# Venus638FLPX-L.net
KiCad netlist of a schematic drawn in EAGLE
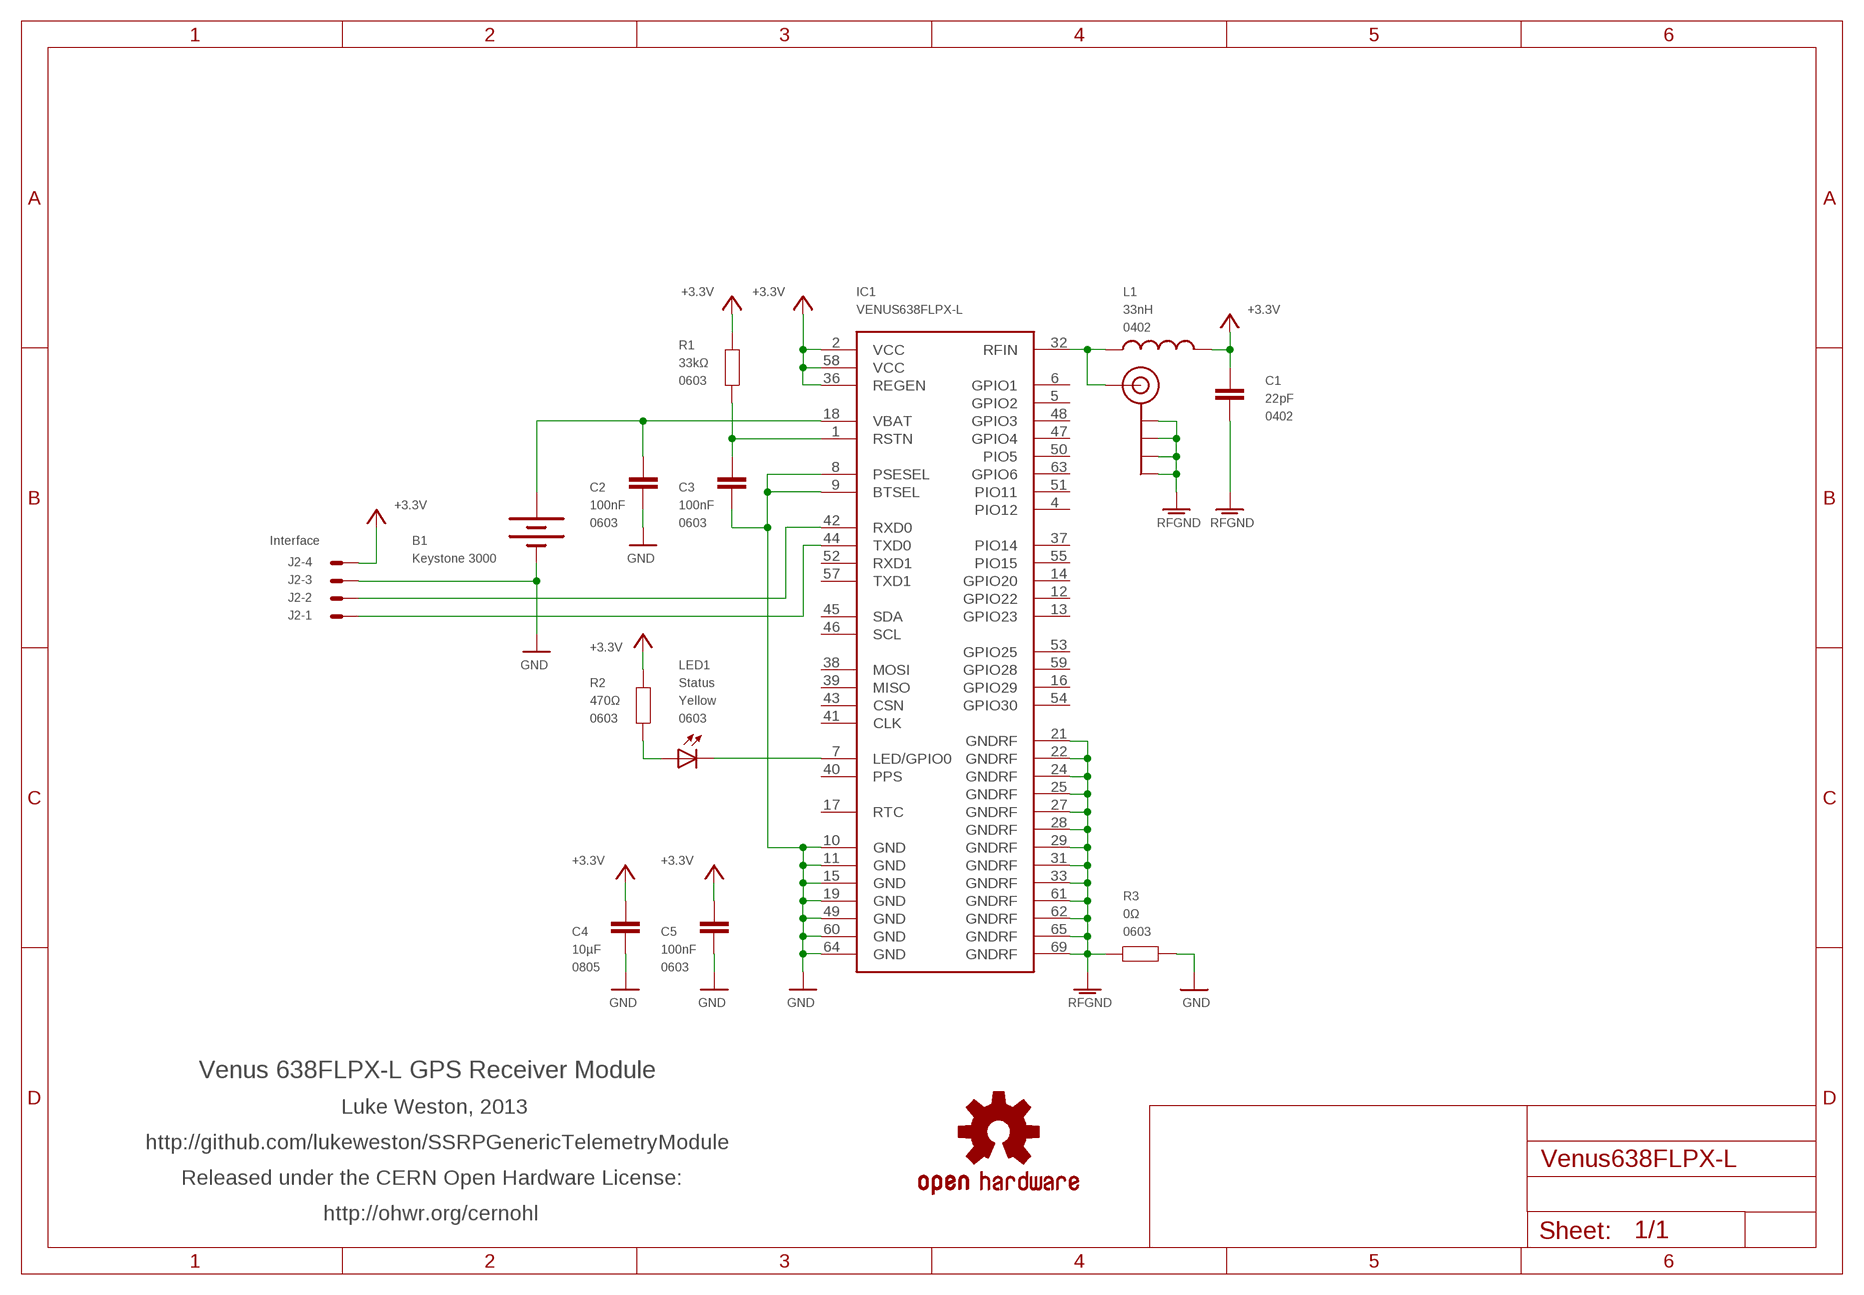
[diagram p0: schematic, sheet 1]

(export (version "E")
  (design (tool "Eeschema 10.0.6"))
  (components
    (comp (ref "B1")
      (value "Keystone 3000")
      (footprint "eagle-import:BATTCON_12MM")
      (libsource (lib "eagle-import") (part "BATTERY12MM"))
    )
    (comp (ref "C1")
      (value "22pF")
      (footprint "eagle-import:C0402")
      (fields (field (name "PACKAGE") "0402"))
      (libsource (lib "eagle-import") (part "CAP0402"))
    )
    (comp (ref "C2")
      (value "100nF")
      (footprint "eagle-import:0603")
      (fields (field (name "PACKAGE") "0603"))
      (libsource (lib "eagle-import") (part "CAP0603"))
    )
    (comp (ref "C3")
      (value "100nF")
      (footprint "eagle-import:0603")
      (fields (field (name "PACKAGE") "0603"))
      (libsource (lib "eagle-import") (part "CAP0603"))
    )
    (comp (ref "C4")
      (value "10µF")
      (footprint "eagle-import:0805")
      (fields (field (name "PACKAGE") "0805"))
      (libsource (lib "eagle-import") (part "CAP0805"))
    )
    (comp (ref "C5")
      (value "100nF")
      (footprint "eagle-import:0603")
      (fields (field (name "PACKAGE") "0603"))
      (libsource (lib "eagle-import") (part "CAP0603"))
    )
    (comp (ref "IC1")
      (value "VENUS638FLPX-L")
      (footprint "eagle-import:VENUS638FLPX")
      (libsource (lib "eagle-import") (part "VENUS638FLPX-L"))
    )
    (comp (ref "J1")
      (value "Antenna")
      (footprint "eagle-import:SMA-EDGE")
      (libsource (lib "eagle-import") (part "SMA_EDGE"))
    )
    (comp (ref "J2")
      (value "Interface")
      (footprint "eagle-import:22-23-2041")
      (fields (field (name "MF") "MOLEX") (field (name "MPN") "22-23-2041"))
      (libsource (lib "eagle-import") (part "22-23-2041"))
    )
    (comp (ref "L1")
      (value "33nH")
      (footprint "eagle-import:C0402")
      (fields (field (name "PACKAGE") "0402"))
      (libsource (lib "eagle-import") (part "INDUCTOR0402"))
    )
    (comp (ref "LED1")
      (value "Status")
      (footprint "eagle-import:LED-0603")
      (fields (field (name "COLOUR") "Yellow") (field (name "PACKAGE") "0603"))
      (libsource (lib "eagle-import") (part "LED0603"))
    )
    (comp (ref "R1")
      (value "33kΩ")
      (footprint "eagle-import:0603")
      (fields (field (name "PACKAGE") "0603"))
      (libsource (lib "eagle-import") (part "RESISTOR0603"))
    )
    (comp (ref "R2")
      (value "470Ω")
      (footprint "eagle-import:0603")
      (fields (field (name "PACKAGE") "0603"))
      (libsource (lib "eagle-import") (part "RESISTOR0603"))
    )
    (comp (ref "R3")
      (value "0Ω")
      (footprint "eagle-import:0603")
      (fields (field (name "PACKAGE") "0603"))
      (libsource (lib "eagle-import") (part "RESISTOR0603"))
    )
    (comp (ref "SY")
      (value "OSHW-LOGOS")
      (footprint "eagle-import:OSHW-LOGO-S")
      (libsource (lib "eagle-import") (part "OSHW-LOGOS"))
    )
  )
  (nets
    (net (code "1") (name "+3.3V") (class "Default")
      (node (ref "C1") (pin "2") (pinfunction "2_2") (pintype "passive"))
      (node (ref "C4") (pin "2") (pinfunction "2_2") (pintype "passive"))
      (node (ref "C5") (pin "2") (pinfunction "2_2") (pintype "passive"))
      (node (ref "IC1") (pin "2") (pinfunction "VCC_2") (pintype "bidirectional"))
      (node (ref "IC1") (pin "36") (pinfunction "REGEN_36") (pintype "bidirectional"))
      (node (ref "IC1") (pin "58") (pinfunction "VCC_58") (pintype "bidirectional"))
      (node (ref "J2") (pin "4") (pinfunction "S_4") (pintype "passive"))
      (node (ref "L1") (pin "1") (pinfunction "1_1") (pintype "passive"))
      (node (ref "R1") (pin "1") (pinfunction "1_1") (pintype "passive"))
      (node (ref "R2") (pin "1") (pinfunction "1_1") (pintype "passive"))
    )
    (net (code "2") (name "GND") (class "Default")
      (node (ref "B1") (pin "GND") (pinfunction "-_GND") (pintype "power_in"))
      (node (ref "C2") (pin "1") (pinfunction "1_1") (pintype "passive"))
      (node (ref "C3") (pin "1") (pinfunction "1_1") (pintype "passive"))
      (node (ref "C4") (pin "1") (pinfunction "1_1") (pintype "passive"))
      (node (ref "C5") (pin "1") (pinfunction "1_1") (pintype "passive"))
      (node (ref "IC1") (pin "10") (pinfunction "GND_10") (pintype "bidirectional"))
      (node (ref "IC1") (pin "11") (pinfunction "GND_11") (pintype "bidirectional"))
      (node (ref "IC1") (pin "15") (pinfunction "GND_15") (pintype "bidirectional"))
      (node (ref "IC1") (pin "19") (pinfunction "GND_19") (pintype "bidirectional"))
      (node (ref "IC1") (pin "49") (pinfunction "GND_49") (pintype "bidirectional"))
      (node (ref "IC1") (pin "60") (pinfunction "GND_60") (pintype "bidirectional"))
      (node (ref "IC1") (pin "64") (pinfunction "GND_64") (pintype "bidirectional"))
      (node (ref "IC1") (pin "8") (pinfunction "PSESEL_8") (pintype "bidirectional"))
      (node (ref "IC1") (pin "9") (pinfunction "BTSEL_9") (pintype "bidirectional"))
      (node (ref "J2") (pin "3") (pinfunction "S_3") (pintype "passive"))
      (node (ref "R3") (pin "1") (pinfunction "1_1") (pintype "passive"))
    )
    (net (code "3") (name "Net-(B1-+)") (class "Default")
      (node (ref "B1") (pin "PWR@1") (pinfunction "+_PWR@1") (pintype "power_in"))
      (node (ref "C2") (pin "2") (pinfunction "2_2") (pintype "passive"))
      (node (ref "IC1") (pin "18") (pinfunction "VBAT_18") (pintype "bidirectional"))
    )
    (net (code "4") (name "Net-(IC1-LED{slash}GPIO0)") (class "Default")
      (node (ref "IC1") (pin "7") (pinfunction "LED/GPIO0_7") (pintype "bidirectional"))
      (node (ref "LED1") (pin "C") (pinfunction "C_C") (pintype "passive"))
    )
    (net (code "5") (name "Net-(IC1-RFIN)") (class "Default")
      (node (ref "IC1") (pin "32") (pinfunction "RFIN_32") (pintype "bidirectional"))
      (node (ref "J1") (pin "SIG") (pinfunction "SIGNAL_SIG") (pintype "bidirectional"))
      (node (ref "L1") (pin "2") (pinfunction "2_2") (pintype "passive"))
    )
    (net (code "6") (name "Net-(IC1-RSTN)") (class "Default")
      (node (ref "C3") (pin "2") (pinfunction "2_2") (pintype "passive"))
      (node (ref "IC1") (pin "1") (pinfunction "RSTN_1") (pintype "bidirectional"))
      (node (ref "R1") (pin "2") (pinfunction "2_2") (pintype "passive"))
    )
    (net (code "7") (name "Net-(IC1-RXD0)") (class "Default")
      (node (ref "IC1") (pin "42") (pinfunction "RXD0_42") (pintype "bidirectional"))
      (node (ref "J2") (pin "2") (pinfunction "S_2") (pintype "passive"))
    )
    (net (code "8") (name "Net-(IC1-TXD0)") (class "Default")
      (node (ref "IC1") (pin "44") (pinfunction "TXD0_44") (pintype "bidirectional"))
      (node (ref "J2") (pin "1") (pinfunction "S_1") (pintype "passive"))
    )
    (net (code "9") (name "Net-(LED1-PadA)") (class "Default")
      (node (ref "LED1") (pin "A") (pinfunction "A_A") (pintype "passive"))
      (node (ref "R2") (pin "2") (pinfunction "2_2") (pintype "passive"))
    )
    (net (code "10") (name "RFGND") (class "Default")
      (node (ref "C1") (pin "1") (pinfunction "1_1") (pintype "passive"))
      (node (ref "IC1") (pin "21") (pinfunction "GNDRF_21") (pintype "bidirectional"))
      (node (ref "IC1") (pin "22") (pinfunction "GNDRF_22") (pintype "bidirectional"))
      (node (ref "IC1") (pin "24") (pinfunction "GNDRF_24") (pintype "bidirectional"))
      (node (ref "IC1") (pin "25") (pinfunction "GNDRF_25") (pintype "bidirectional"))
      (node (ref "IC1") (pin "27") (pinfunction "GNDRF_27") (pintype "bidirectional"))
      (node (ref "IC1") (pin "28") (pinfunction "GNDRF_28") (pintype "bidirectional"))
      (node (ref "IC1") (pin "29") (pinfunction "GNDRF_29") (pintype "bidirectional"))
      (node (ref "IC1") (pin "31") (pinfunction "GNDRF_31") (pintype "bidirectional"))
      (node (ref "IC1") (pin "33") (pinfunction "GNDRF_33") (pintype "bidirectional"))
      (node (ref "IC1") (pin "61") (pinfunction "GNDRF_61") (pintype "bidirectional"))
      (node (ref "IC1") (pin "62") (pinfunction "GNDRF_62") (pintype "bidirectional"))
      (node (ref "IC1") (pin "65") (pinfunction "GNDRF_65") (pintype "bidirectional"))
      (node (ref "IC1") (pin "69") (pinfunction "GNDRF_69") (pintype "bidirectional"))
      (node (ref "J1") (pin "GND@0") (pinfunction "GND_GND@0") (pintype "bidirectional"))
      (node (ref "J1") (pin "GND@1") (pinfunction "GND_GND@1") (pintype "bidirectional"))
      (node (ref "J1") (pin "GND@2") (pinfunction "GND_GND@2") (pintype "bidirectional"))
      (node (ref "J1") (pin "GND@3") (pinfunction "GND_GND@3") (pintype "bidirectional"))
      (node (ref "R3") (pin "2") (pinfunction "2_2") (pintype "passive"))
    )
    (net (code "11") (name "unconnected-(IC1-CLK-Pad41)") (class "Default")
      (node (ref "IC1") (pin "41") (pinfunction "CLK_41") (pintype "bidirectional"))
    )
    (net (code "12") (name "unconnected-(IC1-CSN-Pad43)") (class "Default")
      (node (ref "IC1") (pin "43") (pinfunction "CSN_43") (pintype "bidirectional"))
    )
    (net (code "13") (name "unconnected-(IC1-GPIO1-Pad6)") (class "Default")
      (node (ref "IC1") (pin "6") (pinfunction "GPIO1_6") (pintype "bidirectional"))
    )
    (net (code "14") (name "unconnected-(IC1-GPIO2-Pad5)") (class "Default")
      (node (ref "IC1") (pin "5") (pinfunction "GPIO2_5") (pintype "bidirectional"))
    )
    (net (code "15") (name "unconnected-(IC1-GPIO3-Pad48)") (class "Default")
      (node (ref "IC1") (pin "48") (pinfunction "GPIO3_48") (pintype "bidirectional"))
    )
    (net (code "16") (name "unconnected-(IC1-GPIO4-Pad47)") (class "Default")
      (node (ref "IC1") (pin "47") (pinfunction "GPIO4_47") (pintype "bidirectional"))
    )
    (net (code "17") (name "unconnected-(IC1-GPIO6-Pad63)") (class "Default")
      (node (ref "IC1") (pin "63") (pinfunction "GPIO6_63") (pintype "bidirectional"))
    )
    (net (code "18") (name "unconnected-(IC1-GPIO20-Pad14)") (class "Default")
      (node (ref "IC1") (pin "14") (pinfunction "GPIO20_14") (pintype "bidirectional"))
    )
    (net (code "19") (name "unconnected-(IC1-GPIO22-Pad12)") (class "Default")
      (node (ref "IC1") (pin "12") (pinfunction "GPIO22_12") (pintype "bidirectional"))
    )
    (net (code "20") (name "unconnected-(IC1-GPIO23-Pad13)") (class "Default")
      (node (ref "IC1") (pin "13") (pinfunction "GPIO23_13") (pintype "bidirectional"))
    )
    (net (code "21") (name "unconnected-(IC1-GPIO25-Pad53)") (class "Default")
      (node (ref "IC1") (pin "53") (pinfunction "GPIO25_53") (pintype "bidirectional"))
    )
    (net (code "22") (name "unconnected-(IC1-GPIO28-Pad59)") (class "Default")
      (node (ref "IC1") (pin "59") (pinfunction "GPIO28_59") (pintype "bidirectional"))
    )
    (net (code "23") (name "unconnected-(IC1-GPIO29-Pad16)") (class "Default")
      (node (ref "IC1") (pin "16") (pinfunction "GPIO29_16") (pintype "bidirectional"))
    )
    (net (code "24") (name "unconnected-(IC1-GPIO30-Pad54)") (class "Default")
      (node (ref "IC1") (pin "54") (pinfunction "GPIO30_54") (pintype "bidirectional"))
    )
    (net (code "25") (name "unconnected-(IC1-MISO-Pad39)") (class "Default")
      (node (ref "IC1") (pin "39") (pinfunction "MISO_39") (pintype "bidirectional"))
    )
    (net (code "26") (name "unconnected-(IC1-MOSI-Pad38)") (class "Default")
      (node (ref "IC1") (pin "38") (pinfunction "MOSI_38") (pintype "bidirectional"))
    )
    (net (code "27") (name "unconnected-(IC1-PIO5-Pad50)") (class "Default")
      (node (ref "IC1") (pin "50") (pinfunction "PIO5_50") (pintype "bidirectional"))
    )
    (net (code "28") (name "unconnected-(IC1-PIO11-Pad51)") (class "Default")
      (node (ref "IC1") (pin "51") (pinfunction "PIO11_51") (pintype "bidirectional"))
    )
    (net (code "29") (name "unconnected-(IC1-PIO12-Pad4)") (class "Default")
      (node (ref "IC1") (pin "4") (pinfunction "PIO12_4") (pintype "bidirectional"))
    )
    (net (code "30") (name "unconnected-(IC1-PIO14-Pad37)") (class "Default")
      (node (ref "IC1") (pin "37") (pinfunction "PIO14_37") (pintype "bidirectional"))
    )
    (net (code "31") (name "unconnected-(IC1-PIO15-Pad55)") (class "Default")
      (node (ref "IC1") (pin "55") (pinfunction "PIO15_55") (pintype "bidirectional"))
    )
    (net (code "32") (name "unconnected-(IC1-PPS-Pad40)") (class "Default")
      (node (ref "IC1") (pin "40") (pinfunction "PPS_40") (pintype "bidirectional"))
    )
    (net (code "33") (name "unconnected-(IC1-RTC-Pad17)") (class "Default")
      (node (ref "IC1") (pin "17") (pinfunction "RTC_17") (pintype "bidirectional"))
    )
    (net (code "34") (name "unconnected-(IC1-RXD1-Pad52)") (class "Default")
      (node (ref "IC1") (pin "52") (pinfunction "RXD1_52") (pintype "bidirectional"))
    )
    (net (code "35") (name "unconnected-(IC1-SCL-Pad46)") (class "Default")
      (node (ref "IC1") (pin "46") (pinfunction "SCL_46") (pintype "bidirectional"))
    )
    (net (code "36") (name "unconnected-(IC1-SDA-Pad45)") (class "Default")
      (node (ref "IC1") (pin "45") (pinfunction "SDA_45") (pintype "bidirectional"))
    )
    (net (code "37") (name "unconnected-(IC1-TXD1-Pad57)") (class "Default")
      (node (ref "IC1") (pin "57") (pinfunction "TXD1_57") (pintype "bidirectional"))
    )
  )
)
